# 20_BTB.net
KiCad netlist of a schematic drawn in Altium Designer
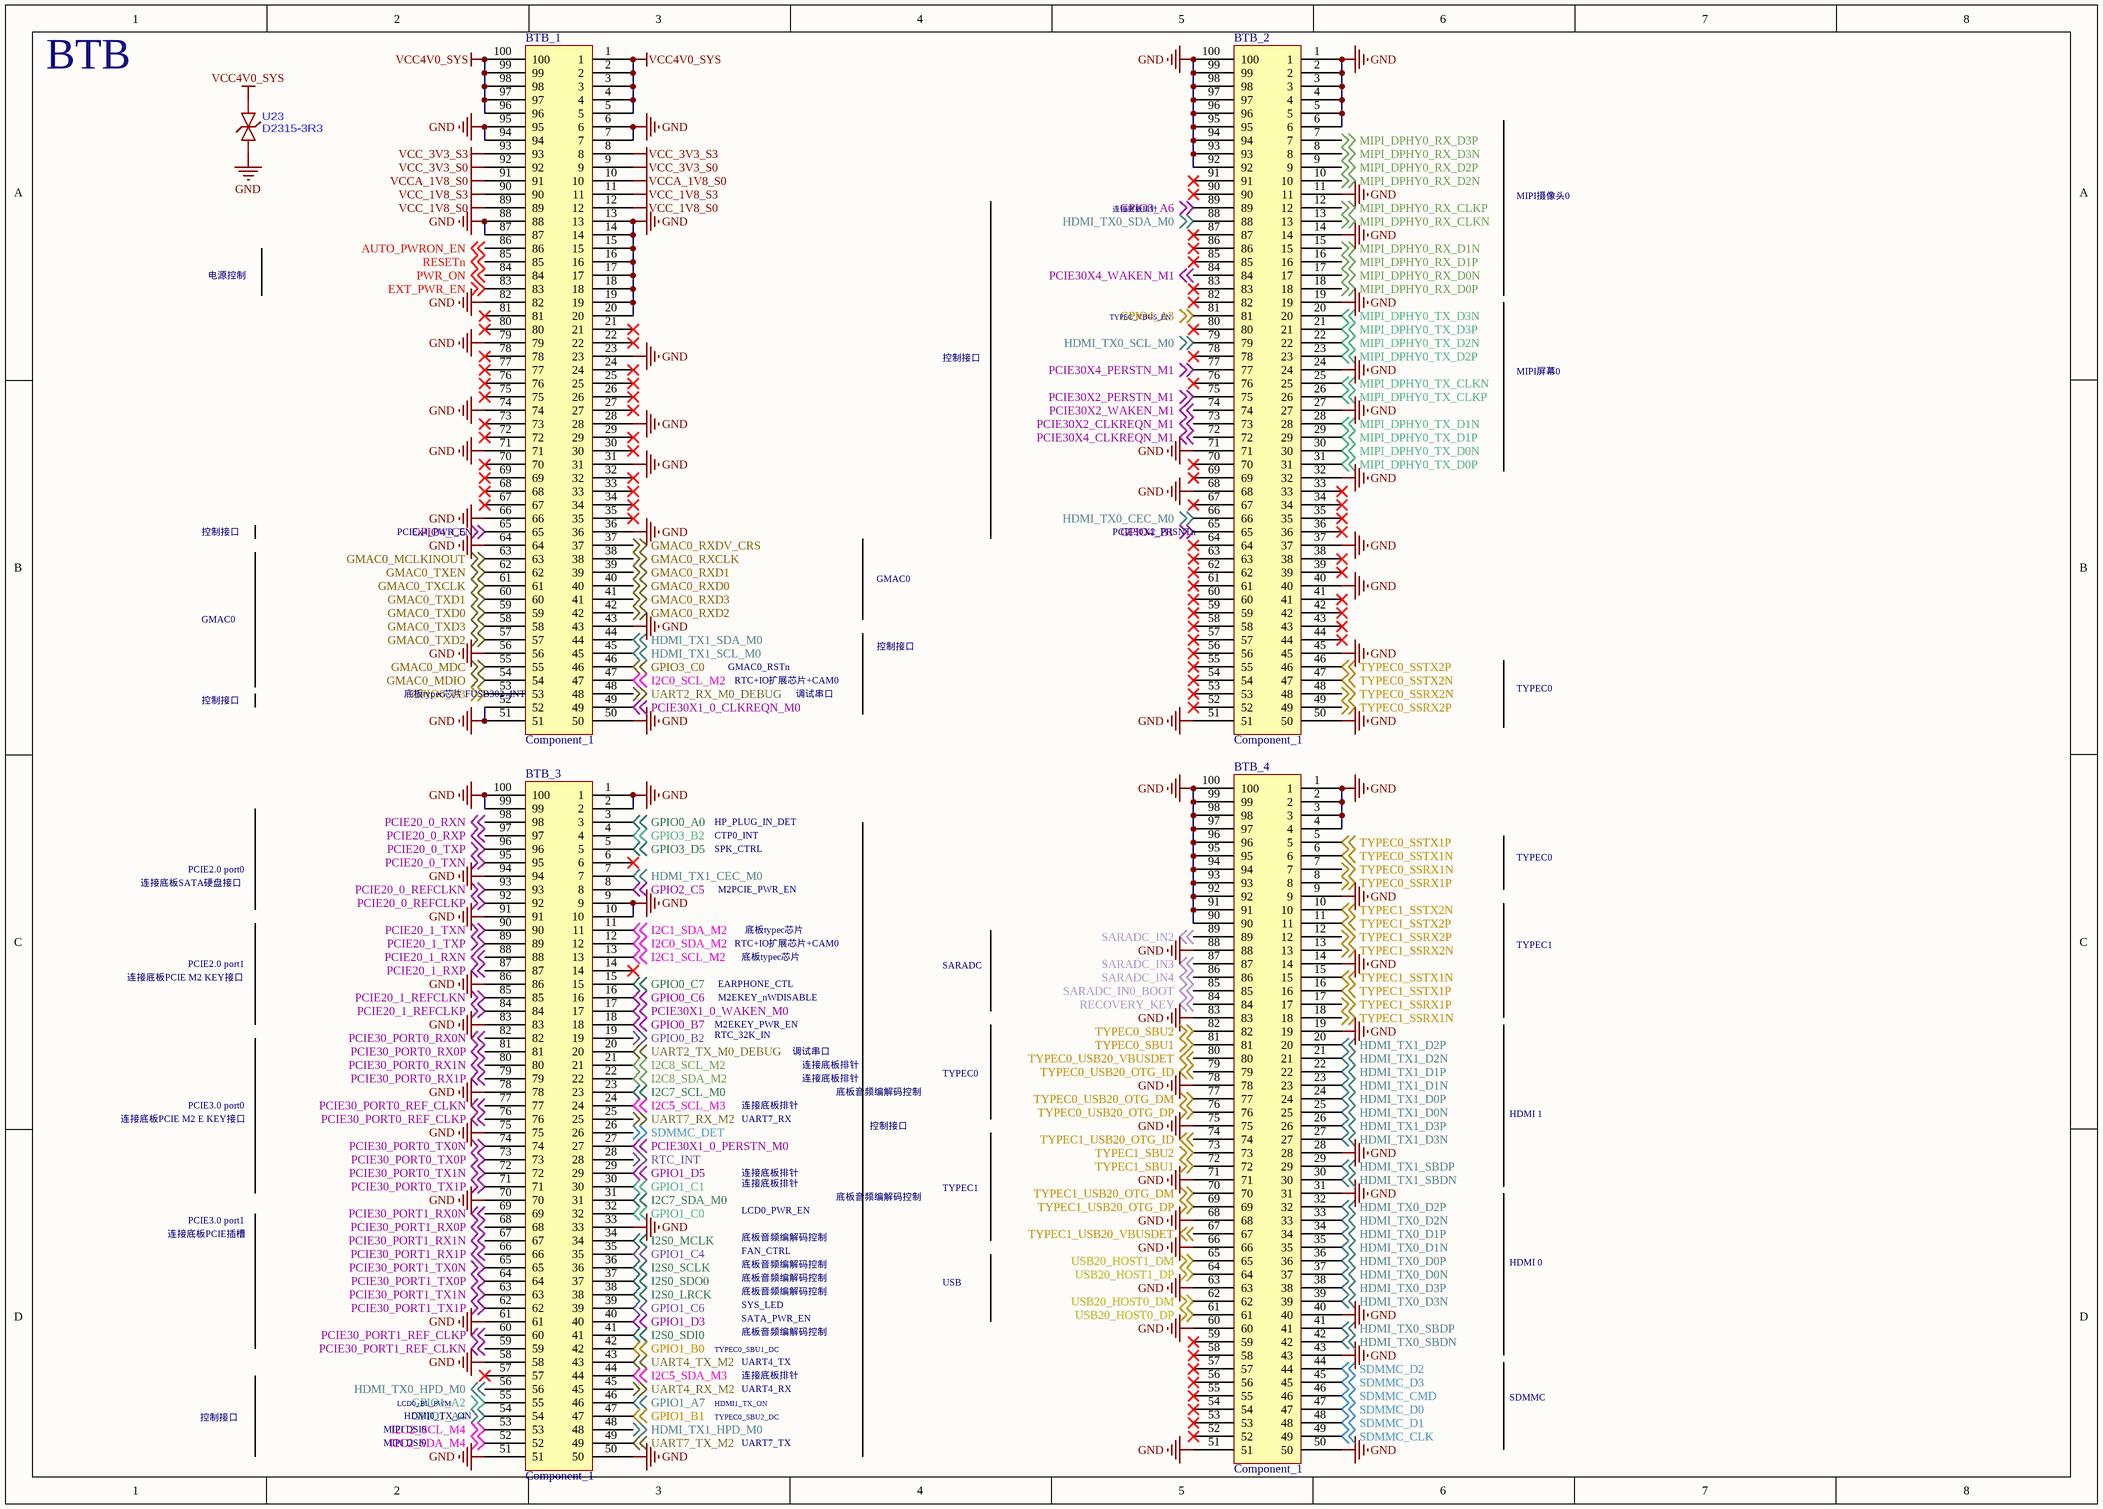
[diagram p0: 20.BTB.SchDoc]

(export (version "E")
  (design (tool "Eeschema 10.0.6"))
  (components
    (comp (ref "BTB_1")
      (value "Component_1")
      (footprint "0.PCB1:F_100PIN")
      (libsource (lib "RK3588") (part "Component_1"))
    )
    (comp (ref "BTB_2")
      (value "Component_1")
      (footprint "0.PCB1:F_100PIN")
      (libsource (lib "RK3588") (part "Component_1"))
    )
    (comp (ref "BTB_3")
      (value "Component_1")
      (footprint "0.PCB1:F_100PIN")
      (libsource (lib "RK3588") (part "Component_1"))
    )
    (comp (ref "BTB_4")
      (value "Component_1")
      (footprint "0.PCB1:F_100PIN")
      (libsource (lib "RK3588") (part "Component_1"))
    )
    (comp (ref "U23")
      (value "D2315-3R3")
      (footprint "0.PCB1:DFN1006-2L-BI")
      (libsource (lib "RK3588") (part "D2315-3R3"))
    )
  )
  (nets
    (net (code "1") (name "AUTO_PWRON_EN") (class "Default")
      (node (ref "BTB_1") (pin "86") (pinfunction "86_86") (pintype "passive"))
    )
    (net (code "2") (name "EXT_PWR_EN") (class "Default")
      (node (ref "BTB_1") (pin "83") (pinfunction "83_83") (pintype "passive"))
    )
    (net (code "3") (name "GMAC0_MCLKINOUT") (class "Default")
      (node (ref "BTB_1") (pin "63") (pinfunction "63_63") (pintype "passive"))
    )
    (net (code "4") (name "GMAC0_MDC") (class "Default")
      (node (ref "BTB_1") (pin "55") (pinfunction "55_55") (pintype "passive"))
    )
    (net (code "5") (name "GMAC0_MDIO") (class "Default")
      (node (ref "BTB_1") (pin "54") (pinfunction "54_54") (pintype "passive"))
    )
    (net (code "6") (name "GMAC0_RXCLK") (class "Default")
      (node (ref "BTB_1") (pin "38") (pinfunction "38_38") (pintype "passive"))
    )
    (net (code "7") (name "GMAC0_RXD0") (class "Default")
      (node (ref "BTB_1") (pin "40") (pinfunction "40_40") (pintype "passive"))
    )
    (net (code "8") (name "GMAC0_RXD1") (class "Default")
      (node (ref "BTB_1") (pin "39") (pinfunction "39_39") (pintype "passive"))
    )
    (net (code "9") (name "GMAC0_RXD2") (class "Default")
      (node (ref "BTB_1") (pin "42") (pinfunction "42_42") (pintype "passive"))
    )
    (net (code "10") (name "GMAC0_RXD3") (class "Default")
      (node (ref "BTB_1") (pin "41") (pinfunction "41_41") (pintype "passive"))
    )
    (net (code "11") (name "GMAC0_RXDV_CRS") (class "Default")
      (node (ref "BTB_1") (pin "37") (pinfunction "37_37") (pintype "passive"))
    )
    (net (code "12") (name "GMAC0_TXCLK") (class "Default")
      (node (ref "BTB_1") (pin "61") (pinfunction "61_61") (pintype "passive"))
    )
    (net (code "13") (name "GMAC0_TXD0") (class "Default")
      (node (ref "BTB_1") (pin "59") (pinfunction "59_59") (pintype "passive"))
    )
    (net (code "14") (name "GMAC0_TXD1") (class "Default")
      (node (ref "BTB_1") (pin "60") (pinfunction "60_60") (pintype "passive"))
    )
    (net (code "15") (name "GMAC0_TXD2") (class "Default")
      (node (ref "BTB_1") (pin "57") (pinfunction "57_57") (pintype "passive"))
    )
    (net (code "16") (name "GMAC0_TXD3") (class "Default")
      (node (ref "BTB_1") (pin "58") (pinfunction "58_58") (pintype "passive"))
    )
    (net (code "17") (name "GMAC0_TXEN") (class "Default")
      (node (ref "BTB_1") (pin "62") (pinfunction "62_62") (pintype "passive"))
    )
    (net (code "18") (name "GND") (class "Default")
      (node (ref "BTB_1") (pin "13") (pinfunction "13_13") (pintype "passive"))
      (node (ref "BTB_1") (pin "14") (pinfunction "14_14") (pintype "passive"))
      (node (ref "BTB_1") (pin "15") (pinfunction "15_15") (pintype "passive"))
      (node (ref "BTB_1") (pin "16") (pinfunction "16_16") (pintype "passive"))
      (node (ref "BTB_1") (pin "17") (pinfunction "17_17") (pintype "passive"))
      (node (ref "BTB_1") (pin "18") (pinfunction "18_18") (pintype "passive"))
      (node (ref "BTB_1") (pin "19") (pinfunction "19_19") (pintype "passive"))
      (node (ref "BTB_1") (pin "20") (pinfunction "20_20") (pintype "passive"))
      (node (ref "BTB_1") (pin "23") (pinfunction "23_23") (pintype "passive"))
      (node (ref "BTB_1") (pin "28") (pinfunction "28_28") (pintype "passive"))
      (node (ref "BTB_1") (pin "31") (pinfunction "31_31") (pintype "passive"))
      (node (ref "BTB_1") (pin "36") (pinfunction "36_36") (pintype "passive"))
      (node (ref "BTB_1") (pin "43") (pinfunction "43_43") (pintype "passive"))
      (node (ref "BTB_1") (pin "50") (pinfunction "50_50") (pintype "passive"))
      (node (ref "BTB_1") (pin "51") (pinfunction "51_51") (pintype "passive"))
      (node (ref "BTB_1") (pin "52") (pinfunction "52_52") (pintype "passive"))
      (node (ref "BTB_1") (pin "56") (pinfunction "56_56") (pintype "passive"))
      (node (ref "BTB_1") (pin "6") (pinfunction "6_6") (pintype "passive"))
      (node (ref "BTB_1") (pin "64") (pinfunction "64_64") (pintype "passive"))
      (node (ref "BTB_1") (pin "66") (pinfunction "66_66") (pintype "passive"))
      (node (ref "BTB_1") (pin "7") (pinfunction "7_7") (pintype "passive"))
      (node (ref "BTB_1") (pin "71") (pinfunction "71_71") (pintype "passive"))
      (node (ref "BTB_1") (pin "74") (pinfunction "74_74") (pintype "passive"))
      (node (ref "BTB_1") (pin "79") (pinfunction "79_79") (pintype "passive"))
      (node (ref "BTB_1") (pin "82") (pinfunction "82_82") (pintype "passive"))
      (node (ref "BTB_1") (pin "87") (pinfunction "87_87") (pintype "passive"))
      (node (ref "BTB_1") (pin "88") (pinfunction "88_88") (pintype "passive"))
      (node (ref "BTB_1") (pin "94") (pinfunction "94_94") (pintype "passive"))
      (node (ref "BTB_1") (pin "95") (pinfunction "95_95") (pintype "passive"))
      (node (ref "BTB_2") (pin "1") (pinfunction "1_1") (pintype "passive"))
      (node (ref "BTB_2") (pin "100") (pinfunction "100_100") (pintype "passive"))
      (node (ref "BTB_2") (pin "11") (pinfunction "11_11") (pintype "passive"))
      (node (ref "BTB_2") (pin "14") (pinfunction "14_14") (pintype "passive"))
      (node (ref "BTB_2") (pin "19") (pinfunction "19_19") (pintype "passive"))
      (node (ref "BTB_2") (pin "2") (pinfunction "2_2") (pintype "passive"))
      (node (ref "BTB_2") (pin "24") (pinfunction "24_24") (pintype "passive"))
      (node (ref "BTB_2") (pin "27") (pinfunction "27_27") (pintype "passive"))
      (node (ref "BTB_2") (pin "3") (pinfunction "3_3") (pintype "passive"))
      (node (ref "BTB_2") (pin "32") (pinfunction "32_32") (pintype "passive"))
      (node (ref "BTB_2") (pin "37") (pinfunction "37_37") (pintype "passive"))
      (node (ref "BTB_2") (pin "4") (pinfunction "4_4") (pintype "passive"))
      (node (ref "BTB_2") (pin "40") (pinfunction "40_40") (pintype "passive"))
      (node (ref "BTB_2") (pin "45") (pinfunction "45_45") (pintype "passive"))
      (node (ref "BTB_2") (pin "5") (pinfunction "5_5") (pintype "passive"))
      (node (ref "BTB_2") (pin "50") (pinfunction "50_50") (pintype "passive"))
      (node (ref "BTB_2") (pin "51") (pinfunction "51_51") (pintype "passive"))
      (node (ref "BTB_2") (pin "6") (pinfunction "6_6") (pintype "passive"))
      (node (ref "BTB_2") (pin "68") (pinfunction "68_68") (pintype "passive"))
      (node (ref "BTB_2") (pin "71") (pinfunction "71_71") (pintype "passive"))
      (node (ref "BTB_2") (pin "92") (pinfunction "92_92") (pintype "passive"))
      (node (ref "BTB_2") (pin "93") (pinfunction "93_93") (pintype "passive"))
      (node (ref "BTB_2") (pin "94") (pinfunction "94_94") (pintype "passive"))
      (node (ref "BTB_2") (pin "95") (pinfunction "95_95") (pintype "passive"))
      (node (ref "BTB_2") (pin "96") (pinfunction "96_96") (pintype "passive"))
      (node (ref "BTB_2") (pin "97") (pinfunction "97_97") (pintype "passive"))
      (node (ref "BTB_2") (pin "98") (pinfunction "98_98") (pintype "passive"))
      (node (ref "BTB_2") (pin "99") (pinfunction "99_99") (pintype "passive"))
      (node (ref "BTB_3") (pin "1") (pinfunction "1_1") (pintype "passive"))
      (node (ref "BTB_3") (pin "10") (pinfunction "10_10") (pintype "passive"))
      (node (ref "BTB_3") (pin "100") (pinfunction "100_100") (pintype "passive"))
      (node (ref "BTB_3") (pin "2") (pinfunction "2_2") (pintype "passive"))
      (node (ref "BTB_3") (pin "33") (pinfunction "33_33") (pintype "passive"))
      (node (ref "BTB_3") (pin "50") (pinfunction "50_50") (pintype "passive"))
      (node (ref "BTB_3") (pin "51") (pinfunction "51_51") (pintype "passive"))
      (node (ref "BTB_3") (pin "58") (pinfunction "58_58") (pintype "passive"))
      (node (ref "BTB_3") (pin "61") (pinfunction "61_61") (pintype "passive"))
      (node (ref "BTB_3") (pin "70") (pinfunction "70_70") (pintype "passive"))
      (node (ref "BTB_3") (pin "75") (pinfunction "75_75") (pintype "passive"))
      (node (ref "BTB_3") (pin "78") (pinfunction "78_78") (pintype "passive"))
      (node (ref "BTB_3") (pin "83") (pinfunction "83_83") (pintype "passive"))
      (node (ref "BTB_3") (pin "86") (pinfunction "86_86") (pintype "passive"))
      (node (ref "BTB_3") (pin "9") (pinfunction "9_9") (pintype "passive"))
      (node (ref "BTB_3") (pin "91") (pinfunction "91_91") (pintype "passive"))
      (node (ref "BTB_3") (pin "94") (pinfunction "94_94") (pintype "passive"))
      (node (ref "BTB_3") (pin "99") (pinfunction "99_99") (pintype "passive"))
      (node (ref "BTB_4") (pin "1") (pinfunction "1_1") (pintype "passive"))
      (node (ref "BTB_4") (pin "100") (pinfunction "100_100") (pintype "passive"))
      (node (ref "BTB_4") (pin "14") (pinfunction "14_14") (pintype "passive"))
      (node (ref "BTB_4") (pin "19") (pinfunction "19_19") (pintype "passive"))
      (node (ref "BTB_4") (pin "2") (pinfunction "2_2") (pintype "passive"))
      (node (ref "BTB_4") (pin "28") (pinfunction "28_28") (pintype "passive"))
      (node (ref "BTB_4") (pin "3") (pinfunction "3_3") (pintype "passive"))
      (node (ref "BTB_4") (pin "31") (pinfunction "31_31") (pintype "passive"))
      (node (ref "BTB_4") (pin "4") (pinfunction "4_4") (pintype "passive"))
      (node (ref "BTB_4") (pin "40") (pinfunction "40_40") (pintype "passive"))
      (node (ref "BTB_4") (pin "43") (pinfunction "43_43") (pintype "passive"))
      (node (ref "BTB_4") (pin "50") (pinfunction "50_50") (pintype "passive"))
      (node (ref "BTB_4") (pin "51") (pinfunction "51_51") (pintype "passive"))
      (node (ref "BTB_4") (pin "60") (pinfunction "60_60") (pintype "passive"))
      (node (ref "BTB_4") (pin "63") (pinfunction "63_63") (pintype "passive"))
      (node (ref "BTB_4") (pin "66") (pinfunction "66_66") (pintype "passive"))
      (node (ref "BTB_4") (pin "68") (pinfunction "68_68") (pintype "passive"))
      (node (ref "BTB_4") (pin "71") (pinfunction "71_71") (pintype "passive"))
      (node (ref "BTB_4") (pin "75") (pinfunction "75_75") (pintype "passive"))
      (node (ref "BTB_4") (pin "78") (pinfunction "78_78") (pintype "passive"))
      (node (ref "BTB_4") (pin "83") (pinfunction "83_83") (pintype "passive"))
      (node (ref "BTB_4") (pin "88") (pinfunction "88_88") (pintype "passive"))
      (node (ref "BTB_4") (pin "9") (pinfunction "9_9") (pintype "passive"))
      (node (ref "BTB_4") (pin "90") (pinfunction "90_90") (pintype "passive"))
      (node (ref "BTB_4") (pin "91") (pinfunction "91_91") (pintype "passive"))
      (node (ref "BTB_4") (pin "92") (pinfunction "92_92") (pintype "passive"))
      (node (ref "BTB_4") (pin "93") (pinfunction "93_93") (pintype "passive"))
      (node (ref "BTB_4") (pin "94") (pinfunction "94_94") (pintype "passive"))
      (node (ref "BTB_4") (pin "95") (pinfunction "95_95") (pintype "passive"))
      (node (ref "BTB_4") (pin "96") (pinfunction "96_96") (pintype "passive"))
      (node (ref "BTB_4") (pin "97") (pinfunction "97_97") (pintype "passive"))
      (node (ref "BTB_4") (pin "98") (pinfunction "98_98") (pintype "passive"))
      (node (ref "BTB_4") (pin "99") (pinfunction "99_99") (pintype "passive"))
      (node (ref "U23") (pin "1") (pinfunction "1_1") (pintype "passive"))
    )
    (net (code "19") (name "GPIO0_A0") (class "Default")
      (node (ref "BTB_3") (pin "3") (pinfunction "3_3") (pintype "passive"))
    )
    (net (code "20") (name "GPIO0_B2") (class "Default")
      (node (ref "BTB_3") (pin "19") (pinfunction "19_19") (pintype "passive"))
    )
    (net (code "21") (name "GPIO0_B7") (class "Default")
      (node (ref "BTB_3") (pin "18") (pinfunction "18_18") (pintype "passive"))
    )
    (net (code "22") (name "GPIO0_C6") (class "Default")
      (node (ref "BTB_3") (pin "16") (pinfunction "16_16") (pintype "passive"))
    )
    (net (code "23") (name "GPIO0_C7") (class "Default")
      (node (ref "BTB_3") (pin "15") (pinfunction "15_15") (pintype "passive"))
    )
    (net (code "24") (name "GPIO0_D3") (class "Default")
      (node (ref "BTB_1") (pin "53") (pinfunction "53_53") (pintype "passive"))
    )
    (net (code "25") (name "GPIO1_A2") (class "Default")
      (node (ref "BTB_3") (pin "55") (pinfunction "55_55") (pintype "passive"))
    )
    (net (code "26") (name "GPIO1_A4") (class "Default")
      (node (ref "BTB_3") (pin "54") (pinfunction "54_54") (pintype "passive"))
    )
    (net (code "27") (name "GPIO1_A7") (class "Default")
      (node (ref "BTB_3") (pin "46") (pinfunction "46_46") (pintype "passive"))
    )
    (net (code "28") (name "GPIO1_B0") (class "Default")
      (node (ref "BTB_3") (pin "42") (pinfunction "42_42") (pintype "passive"))
    )
    (net (code "29") (name "GPIO1_B1") (class "Default")
      (node (ref "BTB_3") (pin "47") (pinfunction "47_47") (pintype "passive"))
    )
    (net (code "30") (name "GPIO1_C0") (class "Default")
      (node (ref "BTB_3") (pin "32") (pinfunction "32_32") (pintype "passive"))
    )
    (net (code "31") (name "GPIO1_C1") (class "Default")
      (node (ref "BTB_3") (pin "30") (pinfunction "30_30") (pintype "passive"))
    )
    (net (code "32") (name "GPIO1_C4") (class "Default")
      (node (ref "BTB_3") (pin "35") (pinfunction "35_35") (pintype "passive"))
    )
    (net (code "33") (name "GPIO1_C6") (class "Default")
      (node (ref "BTB_3") (pin "39") (pinfunction "39_39") (pintype "passive"))
    )
    (net (code "34") (name "GPIO1_D3") (class "Default")
      (node (ref "BTB_3") (pin "40") (pinfunction "40_40") (pintype "passive"))
    )
    (net (code "35") (name "GPIO1_D5") (class "Default")
      (node (ref "BTB_3") (pin "29") (pinfunction "29_29") (pintype "passive"))
    )
    (net (code "36") (name "GPIO2_C5") (class "Default")
      (node (ref "BTB_3") (pin "8") (pinfunction "8_8") (pintype "passive"))
    )
    (net (code "37") (name "GPIO3_A6") (class "Default")
      (node (ref "BTB_2") (pin "89") (pinfunction "89_89") (pintype "passive"))
    )
    (net (code "38") (name "GPIO3_B2") (class "Default")
      (node (ref "BTB_3") (pin "4") (pinfunction "4_4") (pintype "passive"))
    )
    (net (code "39") (name "GPIO3_C0") (class "Default")
      (node (ref "BTB_1") (pin "46") (pinfunction "46_46") (pintype "passive"))
    )
    (net (code "40") (name "GPIO3_D5") (class "Default")
      (node (ref "BTB_3") (pin "5") (pinfunction "5_5") (pintype "passive"))
    )
    (net (code "41") (name "GPIO4_A3") (class "Default")
      (node (ref "BTB_2") (pin "81") (pinfunction "81_81") (pintype "passive"))
    )
    (net (code "42") (name "GPIO4_B1") (class "Default")
      (node (ref "BTB_2") (pin "65") (pinfunction "65_65") (pintype "passive"))
    )
    (net (code "43") (name "GPIO4_C6") (class "Default")
      (node (ref "BTB_1") (pin "65") (pinfunction "65_65") (pintype "passive"))
    )
    (net (code "44") (name "HDMI_TX0_CEC_M0") (class "Default")
      (node (ref "BTB_2") (pin "66") (pinfunction "66_66") (pintype "passive"))
    )
    (net (code "45") (name "HDMI_TX0_D0N") (class "Default")
      (node (ref "BTB_4") (pin "37") (pinfunction "37_37") (pintype "passive"))
    )
    (net (code "46") (name "HDMI_TX0_D0P") (class "Default")
      (node (ref "BTB_4") (pin "36") (pinfunction "36_36") (pintype "passive"))
    )
    (net (code "47") (name "HDMI_TX0_D1N") (class "Default")
      (node (ref "BTB_4") (pin "35") (pinfunction "35_35") (pintype "passive"))
    )
    (net (code "48") (name "HDMI_TX0_D1P") (class "Default")
      (node (ref "BTB_4") (pin "34") (pinfunction "34_34") (pintype "passive"))
    )
    (net (code "49") (name "HDMI_TX0_D2N") (class "Default")
      (node (ref "BTB_4") (pin "33") (pinfunction "33_33") (pintype "passive"))
    )
    (net (code "50") (name "HDMI_TX0_D2P") (class "Default")
      (node (ref "BTB_4") (pin "32") (pinfunction "32_32") (pintype "passive"))
    )
    (net (code "51") (name "HDMI_TX0_D3N") (class "Default")
      (node (ref "BTB_4") (pin "39") (pinfunction "39_39") (pintype "passive"))
    )
    (net (code "52") (name "HDMI_TX0_D3P") (class "Default")
      (node (ref "BTB_4") (pin "38") (pinfunction "38_38") (pintype "passive"))
    )
    (net (code "53") (name "HDMI_TX0_HPD_M0") (class "Default")
      (node (ref "BTB_3") (pin "56") (pinfunction "56_56") (pintype "passive"))
    )
    (net (code "54") (name "HDMI_TX0_SBDN") (class "Default")
      (node (ref "BTB_4") (pin "42") (pinfunction "42_42") (pintype "passive"))
    )
    (net (code "55") (name "HDMI_TX0_SBDP") (class "Default")
      (node (ref "BTB_4") (pin "41") (pinfunction "41_41") (pintype "passive"))
    )
    (net (code "56") (name "HDMI_TX0_SCL_M0") (class "Default")
      (node (ref "BTB_2") (pin "79") (pinfunction "79_79") (pintype "passive"))
    )
    (net (code "57") (name "HDMI_TX0_SDA_M0") (class "Default")
      (node (ref "BTB_2") (pin "88") (pinfunction "88_88") (pintype "passive"))
    )
    (net (code "58") (name "HDMI_TX1_CEC_M0") (class "Default")
      (node (ref "BTB_3") (pin "7") (pinfunction "7_7") (pintype "passive"))
    )
    (net (code "59") (name "HDMI_TX1_D0N") (class "Default")
      (node (ref "BTB_4") (pin "25") (pinfunction "25_25") (pintype "passive"))
    )
    (net (code "60") (name "HDMI_TX1_D0P") (class "Default")
      (node (ref "BTB_4") (pin "24") (pinfunction "24_24") (pintype "passive"))
    )
    (net (code "61") (name "HDMI_TX1_D1N") (class "Default")
      (node (ref "BTB_4") (pin "23") (pinfunction "23_23") (pintype "passive"))
    )
    (net (code "62") (name "HDMI_TX1_D1P") (class "Default")
      (node (ref "BTB_4") (pin "22") (pinfunction "22_22") (pintype "passive"))
    )
    (net (code "63") (name "HDMI_TX1_D2N") (class "Default")
      (node (ref "BTB_4") (pin "21") (pinfunction "21_21") (pintype "passive"))
    )
    (net (code "64") (name "HDMI_TX1_D2P") (class "Default")
      (node (ref "BTB_4") (pin "20") (pinfunction "20_20") (pintype "passive"))
    )
    (net (code "65") (name "HDMI_TX1_D3N") (class "Default")
      (node (ref "BTB_4") (pin "27") (pinfunction "27_27") (pintype "passive"))
    )
    (net (code "66") (name "HDMI_TX1_D3P") (class "Default")
      (node (ref "BTB_4") (pin "26") (pinfunction "26_26") (pintype "passive"))
    )
    (net (code "67") (name "HDMI_TX1_HPD_M0") (class "Default")
      (node (ref "BTB_3") (pin "48") (pinfunction "48_48") (pintype "passive"))
    )
    (net (code "68") (name "HDMI_TX1_SBDN") (class "Default")
      (node (ref "BTB_4") (pin "30") (pinfunction "30_30") (pintype "passive"))
    )
    (net (code "69") (name "HDMI_TX1_SBDP") (class "Default")
      (node (ref "BTB_4") (pin "29") (pinfunction "29_29") (pintype "passive"))
    )
    (net (code "70") (name "HDMI_TX1_SCL_M0") (class "Default")
      (node (ref "BTB_1") (pin "45") (pinfunction "45_45") (pintype "passive"))
    )
    (net (code "71") (name "HDMI_TX1_SDA_M0") (class "Default")
      (node (ref "BTB_1") (pin "44") (pinfunction "44_44") (pintype "passive"))
    )
    (net (code "72") (name "I2C0_SCL_M2") (class "Default")
      (node (ref "BTB_1") (pin "47") (pinfunction "47_47") (pintype "passive"))
    )
    (net (code "73") (name "I2C0_SDA_M2") (class "Default")
      (node (ref "BTB_3") (pin "12") (pinfunction "12_12") (pintype "passive"))
    )
    (net (code "74") (name "I2C1_SCL_M2") (class "Default")
      (node (ref "BTB_3") (pin "13") (pinfunction "13_13") (pintype "passive"))
    )
    (net (code "75") (name "I2C1_SDA_M2") (class "Default")
      (node (ref "BTB_3") (pin "11") (pinfunction "11_11") (pintype "passive"))
    )
    (net (code "76") (name "I2C2_SCL_M4") (class "Default")
      (node (ref "BTB_3") (pin "53") (pinfunction "53_53") (pintype "passive"))
    )
    (net (code "77") (name "I2C2_SDA_M4") (class "Default")
      (node (ref "BTB_3") (pin "52") (pinfunction "52_52") (pintype "passive"))
    )
    (net (code "78") (name "I2C5_SCL_M3") (class "Default")
      (node (ref "BTB_3") (pin "24") (pinfunction "24_24") (pintype "passive"))
    )
    (net (code "79") (name "I2C5_SDA_M3") (class "Default")
      (node (ref "BTB_3") (pin "44") (pinfunction "44_44") (pintype "passive"))
    )
    (net (code "80") (name "I2C7_SCL_M0") (class "Default")
      (node (ref "BTB_3") (pin "23") (pinfunction "23_23") (pintype "passive"))
    )
    (net (code "81") (name "I2C7_SDA_M0") (class "Default")
      (node (ref "BTB_3") (pin "31") (pinfunction "31_31") (pintype "passive"))
    )
    (net (code "82") (name "I2C8_SCL_M2") (class "Default")
      (node (ref "BTB_3") (pin "21") (pinfunction "21_21") (pintype "passive"))
    )
    (net (code "83") (name "I2C8_SDA_M2") (class "Default")
      (node (ref "BTB_3") (pin "22") (pinfunction "22_22") (pintype "passive"))
    )
    (net (code "84") (name "I2S0_LRCK") (class "Default")
      (node (ref "BTB_3") (pin "38") (pinfunction "38_38") (pintype "passive"))
    )
    (net (code "85") (name "I2S0_MCLK") (class "Default")
      (node (ref "BTB_3") (pin "34") (pinfunction "34_34") (pintype "passive"))
    )
    (net (code "86") (name "I2S0_SCLK") (class "Default")
      (node (ref "BTB_3") (pin "36") (pinfunction "36_36") (pintype "passive"))
    )
    (net (code "87") (name "I2S0_SDI0") (class "Default")
      (node (ref "BTB_3") (pin "41") (pinfunction "41_41") (pintype "passive"))
    )
    (net (code "88") (name "I2S0_SDO0") (class "Default")
      (node (ref "BTB_3") (pin "37") (pinfunction "37_37") (pintype "passive"))
    )
    (net (code "89") (name "MIPI_DPHY0_RX_CLKN") (class "Default")
      (node (ref "BTB_2") (pin "13") (pinfunction "13_13") (pintype "passive"))
    )
    (net (code "90") (name "MIPI_DPHY0_RX_CLKP") (class "Default")
      (node (ref "BTB_2") (pin "12") (pinfunction "12_12") (pintype "passive"))
    )
    (net (code "91") (name "MIPI_DPHY0_RX_D0N") (class "Default")
      (node (ref "BTB_2") (pin "17") (pinfunction "17_17") (pintype "passive"))
    )
    (net (code "92") (name "MIPI_DPHY0_RX_D0P") (class "Default")
      (node (ref "BTB_2") (pin "18") (pinfunction "18_18") (pintype "passive"))
    )
    (net (code "93") (name "MIPI_DPHY0_RX_D1N") (class "Default")
      (node (ref "BTB_2") (pin "15") (pinfunction "15_15") (pintype "passive"))
    )
    (net (code "94") (name "MIPI_DPHY0_RX_D1P") (class "Default")
      (node (ref "BTB_2") (pin "16") (pinfunction "16_16") (pintype "passive"))
    )
    (net (code "95") (name "MIPI_DPHY0_RX_D2N") (class "Default")
      (node (ref "BTB_2") (pin "10") (pinfunction "10_10") (pintype "passive"))
    )
    (net (code "96") (name "MIPI_DPHY0_RX_D2P") (class "Default")
      (node (ref "BTB_2") (pin "9") (pinfunction "9_9") (pintype "passive"))
    )
    (net (code "97") (name "MIPI_DPHY0_RX_D3N") (class "Default")
      (node (ref "BTB_2") (pin "8") (pinfunction "8_8") (pintype "passive"))
    )
    (net (code "98") (name "MIPI_DPHY0_RX_D3P") (class "Default")
      (node (ref "BTB_2") (pin "7") (pinfunction "7_7") (pintype "passive"))
    )
    (net (code "99") (name "MIPI_DPHY0_TX_CLKN") (class "Default")
      (node (ref "BTB_2") (pin "25") (pinfunction "25_25") (pintype "passive"))
    )
    (net (code "100") (name "MIPI_DPHY0_TX_CLKP") (class "Default")
      (node (ref "BTB_2") (pin "26") (pinfunction "26_26") (pintype "passive"))
    )
    (net (code "101") (name "MIPI_DPHY0_TX_D0N") (class "Default")
      (node (ref "BTB_2") (pin "30") (pinfunction "30_30") (pintype "passive"))
    )
    (net (code "102") (name "MIPI_DPHY0_TX_D0P") (class "Default")
      (node (ref "BTB_2") (pin "31") (pinfunction "31_31") (pintype "passive"))
    )
    (net (code "103") (name "MIPI_DPHY0_TX_D1N") (class "Default")
      (node (ref "BTB_2") (pin "28") (pinfunction "28_28") (pintype "passive"))
    )
    (net (code "104") (name "MIPI_DPHY0_TX_D1P") (class "Default")
      (node (ref "BTB_2") (pin "29") (pinfunction "29_29") (pintype "passive"))
    )
    (net (code "105") (name "MIPI_DPHY0_TX_D2N") (class "Default")
      (node (ref "BTB_2") (pin "22") (pinfunction "22_22") (pintype "passive"))
    )
    (net (code "106") (name "MIPI_DPHY0_TX_D2P") (class "Default")
      (node (ref "BTB_2") (pin "23") (pinfunction "23_23") (pintype "passive"))
    )
    (net (code "107") (name "MIPI_DPHY0_TX_D3N") (class "Default")
      (node (ref "BTB_2") (pin "20") (pinfunction "20_20") (pintype "passive"))
    )
    (net (code "108") (name "MIPI_DPHY0_TX_D3P") (class "Default")
      (node (ref "BTB_2") (pin "21") (pinfunction "21_21") (pintype "passive"))
    )
    (net (code "109") (name "PCIE20_0_REFCLKN") (class "Default")
      (node (ref "BTB_3") (pin "93") (pinfunction "93_93") (pintype "passive"))
    )
    (net (code "110") (name "PCIE20_0_REFCLKP") (class "Default")
      (node (ref "BTB_3") (pin "92") (pinfunction "92_92") (pintype "passive"))
    )
    (net (code "111") (name "PCIE20_0_RXN") (class "Default")
      (node (ref "BTB_3") (pin "98") (pinfunction "98_98") (pintype "passive"))
    )
    (net (code "112") (name "PCIE20_0_RXP") (class "Default")
      (node (ref "BTB_3") (pin "97") (pinfunction "97_97") (pintype "passive"))
    )
    (net (code "113") (name "PCIE20_0_TXN") (class "Default")
      (node (ref "BTB_3") (pin "95") (pinfunction "95_95") (pintype "passive"))
    )
    (net (code "114") (name "PCIE20_0_TXP") (class "Default")
      (node (ref "BTB_3") (pin "96") (pinfunction "96_96") (pintype "passive"))
    )
    (net (code "115") (name "PCIE20_1_REFCLKN") (class "Default")
      (node (ref "BTB_3") (pin "85") (pinfunction "85_85") (pintype "passive"))
    )
    (net (code "116") (name "PCIE20_1_REFCLKP") (class "Default")
      (node (ref "BTB_3") (pin "84") (pinfunction "84_84") (pintype "passive"))
    )
    (net (code "117") (name "PCIE20_1_RXN") (class "Default")
      (node (ref "BTB_3") (pin "88") (pinfunction "88_88") (pintype "passive"))
    )
    (net (code "118") (name "PCIE20_1_RXP") (class "Default")
      (node (ref "BTB_3") (pin "87") (pinfunction "87_87") (pintype "passive"))
    )
    (net (code "119") (name "PCIE20_1_TXN") (class "Default")
      (node (ref "BTB_3") (pin "90") (pinfunction "90_90") (pintype "passive"))
    )
    (net (code "120") (name "PCIE20_1_TXP") (class "Default")
      (node (ref "BTB_3") (pin "89") (pinfunction "89_89") (pintype "passive"))
    )
    (net (code "121") (name "PCIE30X1_0_CLKREQN_M0") (class "Default")
      (node (ref "BTB_1") (pin "49") (pinfunction "49_49") (pintype "passive"))
    )
    (net (code "122") (name "PCIE30X1_0_PERSTN_M0") (class "Default")
      (node (ref "BTB_3") (pin "27") (pinfunction "27_27") (pintype "passive"))
    )
    (net (code "123") (name "PCIE30X1_0_WAKEN_M0") (class "Default")
      (node (ref "BTB_3") (pin "17") (pinfunction "17_17") (pintype "passive"))
    )
    (net (code "124") (name "PCIE30X2_CLKREQN_M1") (class "Default")
      (node (ref "BTB_2") (pin "73") (pinfunction "73_73") (pintype "passive"))
    )
    (net (code "125") (name "PCIE30X2_PERSTN_M1") (class "Default")
      (node (ref "BTB_2") (pin "75") (pinfunction "75_75") (pintype "passive"))
    )
    (net (code "126") (name "PCIE30X2_WAKEN_M1") (class "Default")
      (node (ref "BTB_2") (pin "74") (pinfunction "74_74") (pintype "passive"))
    )
    (net (code "127") (name "PCIE30X4_CLKREQN_M1") (class "Default")
      (node (ref "BTB_2") (pin "72") (pinfunction "72_72") (pintype "passive"))
    )
    (net (code "128") (name "PCIE30X4_PERSTN_M1") (class "Default")
      (node (ref "BTB_2") (pin "77") (pinfunction "77_77") (pintype "passive"))
    )
    (net (code "129") (name "PCIE30X4_WAKEN_M1") (class "Default")
      (node (ref "BTB_2") (pin "84") (pinfunction "84_84") (pintype "passive"))
    )
    (net (code "130") (name "PCIE30_PORT0_REF_CLKN") (class "Default")
      (node (ref "BTB_3") (pin "77") (pinfunction "77_77") (pintype "passive"))
    )
    (net (code "131") (name "PCIE30_PORT0_REF_CLKP") (class "Default")
      (node (ref "BTB_3") (pin "76") (pinfunction "76_76") (pintype "passive"))
    )
    (net (code "132") (name "PCIE30_PORT0_RX0N") (class "Default")
      (node (ref "BTB_3") (pin "82") (pinfunction "82_82") (pintype "passive"))
    )
    (net (code "133") (name "PCIE30_PORT0_RX0P") (class "Default")
      (node (ref "BTB_3") (pin "81") (pinfunction "81_81") (pintype "passive"))
    )
    (net (code "134") (name "PCIE30_PORT0_RX1N") (class "Default")
      (node (ref "BTB_3") (pin "80") (pinfunction "80_80") (pintype "passive"))
    )
    (net (code "135") (name "PCIE30_PORT0_RX1P") (class "Default")
      (node (ref "BTB_3") (pin "79") (pinfunction "79_79") (pintype "passive"))
    )
    (net (code "136") (name "PCIE30_PORT0_TX0N") (class "Default")
      (node (ref "BTB_3") (pin "74") (pinfunction "74_74") (pintype "passive"))
    )
    (net (code "137") (name "PCIE30_PORT0_TX0P") (class "Default")
      (node (ref "BTB_3") (pin "73") (pinfunction "73_73") (pintype "passive"))
    )
    (net (code "138") (name "PCIE30_PORT0_TX1N") (class "Default")
      (node (ref "BTB_3") (pin "72") (pinfunction "72_72") (pintype "passive"))
    )
    (net (code "139") (name "PCIE30_PORT0_TX1P") (class "Default")
      (node (ref "BTB_3") (pin "71") (pinfunction "71_71") (pintype "passive"))
    )
    (net (code "140") (name "PCIE30_PORT1_REF_CLKN") (class "Default")
      (node (ref "BTB_3") (pin "59") (pinfunction "59_59") (pintype "passive"))
    )
    (net (code "141") (name "PCIE30_PORT1_REF_CLKP") (class "Default")
      (node (ref "BTB_3") (pin "60") (pinfunction "60_60") (pintype "passive"))
    )
    (net (code "142") (name "PCIE30_PORT1_RX0N") (class "Default")
      (node (ref "BTB_3") (pin "69") (pinfunction "69_69") (pintype "passive"))
    )
    (net (code "143") (name "PCIE30_PORT1_RX0P") (class "Default")
      (node (ref "BTB_3") (pin "68") (pinfunction "68_68") (pintype "passive"))
    )
    (net (code "144") (name "PCIE30_PORT1_RX1N") (class "Default")
      (node (ref "BTB_3") (pin "67") (pinfunction "67_67") (pintype "passive"))
    )
    (net (code "145") (name "PCIE30_PORT1_RX1P") (class "Default")
      (node (ref "BTB_3") (pin "66") (pinfunction "66_66") (pintype "passive"))
    )
    (net (code "146") (name "PCIE30_PORT1_TX0N") (class "Default")
      (node (ref "BTB_3") (pin "65") (pinfunction "65_65") (pintype "passive"))
    )
    (net (code "147") (name "PCIE30_PORT1_TX0P") (class "Default")
      (node (ref "BTB_3") (pin "64") (pinfunction "64_64") (pintype "passive"))
    )
    (net (code "148") (name "PCIE30_PORT1_TX1N") (class "Default")
      (node (ref "BTB_3") (pin "63") (pinfunction "63_63") (pintype "passive"))
    )
    (net (code "149") (name "PCIE30_PORT1_TX1P") (class "Default")
      (node (ref "BTB_3") (pin "62") (pinfunction "62_62") (pintype "passive"))
    )
    (net (code "150") (name "PWR_ON") (class "Default")
      (node (ref "BTB_1") (pin "84") (pinfunction "84_84") (pintype "passive"))
    )
    (net (code "151") (name "RECOVERY_KEY") (class "Default")
      (node (ref "BTB_4") (pin "84") (pinfunction "84_84") (pintype "passive"))
    )
    (net (code "152") (name "RESETn") (class "Default")
      (node (ref "BTB_1") (pin "85") (pinfunction "85_85") (pintype "passive"))
    )
    (net (code "153") (name "RTC_INT") (class "Default")
      (node (ref "BTB_3") (pin "28") (pinfunction "28_28") (pintype "passive"))
    )
    (net (code "154") (name "SARADC_IN0_BOOT") (class "Default")
      (node (ref "BTB_4") (pin "85") (pinfunction "85_85") (pintype "passive"))
    )
    (net (code "155") (name "SARADC_IN2") (class "Default")
      (node (ref "BTB_4") (pin "89") (pinfunction "89_89") (pintype "passive"))
    )
    (net (code "156") (name "SARADC_IN3") (class "Default")
      (node (ref "BTB_4") (pin "87") (pinfunction "87_87") (pintype "passive"))
    )
    (net (code "157") (name "SARADC_IN4") (class "Default")
      (node (ref "BTB_4") (pin "86") (pinfunction "86_86") (pintype "passive"))
    )
    (net (code "158") (name "SDMMC_CLK") (class "Default")
      (node (ref "BTB_4") (pin "49") (pinfunction "49_49") (pintype "passive"))
    )
    (net (code "159") (name "SDMMC_CMD") (class "Default")
      (node (ref "BTB_4") (pin "46") (pinfunction "46_46") (pintype "passive"))
    )
    (net (code "160") (name "SDMMC_D0") (class "Default")
      (node (ref "BTB_4") (pin "47") (pinfunction "47_47") (pintype "passive"))
    )
    (net (code "161") (name "SDMMC_D1") (class "Default")
      (node (ref "BTB_4") (pin "48") (pinfunction "48_48") (pintype "passive"))
    )
    (net (code "162") (name "SDMMC_D2") (class "Default")
      (node (ref "BTB_4") (pin "44") (pinfunction "44_44") (pintype "passive"))
    )
    (net (code "163") (name "SDMMC_D3") (class "Default")
      (node (ref "BTB_4") (pin "45") (pinfunction "45_45") (pintype "passive"))
    )
    (net (code "164") (name "SDMMC_DET") (class "Default")
      (node (ref "BTB_3") (pin "26") (pinfunction "26_26") (pintype "passive"))
    )
    (net (code "165") (name "TYPEC0_SBU1") (class "Default")
      (node (ref "BTB_4") (pin "81") (pinfunction "81_81") (pintype "passive"))
    )
    (net (code "166") (name "TYPEC0_SBU2") (class "Default")
      (node (ref "BTB_4") (pin "82") (pinfunction "82_82") (pintype "passive"))
    )
    (net (code "167") (name "TYPEC0_SSRX1N") (class "Default")
      (node (ref "BTB_4") (pin "7") (pinfunction "7_7") (pintype "passive"))
    )
    (net (code "168") (name "TYPEC0_SSRX1P") (class "Default")
      (node (ref "BTB_4") (pin "8") (pinfunction "8_8") (pintype "passive"))
    )
    (net (code "169") (name "TYPEC0_SSRX2N") (class "Default")
      (node (ref "BTB_2") (pin "48") (pinfunction "48_48") (pintype "passive"))
    )
    (net (code "170") (name "TYPEC0_SSRX2P") (class "Default")
      (node (ref "BTB_2") (pin "49") (pinfunction "49_49") (pintype "passive"))
    )
    (net (code "171") (name "TYPEC0_SSTX1N") (class "Default")
      (node (ref "BTB_4") (pin "6") (pinfunction "6_6") (pintype "passive"))
    )
    (net (code "172") (name "TYPEC0_SSTX1P") (class "Default")
      (node (ref "BTB_4") (pin "5") (pinfunction "5_5") (pintype "passive"))
    )
    (net (code "173") (name "TYPEC0_SSTX2N") (class "Default")
      (node (ref "BTB_2") (pin "47") (pinfunction "47_47") (pintype "passive"))
    )
    (net (code "174") (name "TYPEC0_SSTX2P") (class "Default")
      (node (ref "BTB_2") (pin "46") (pinfunction "46_46") (pintype "passive"))
    )
    (net (code "175") (name "TYPEC0_USB20_OTG_DM") (class "Default")
      (node (ref "BTB_4") (pin "77") (pinfunction "77_77") (pintype "passive"))
    )
    (net (code "176") (name "TYPEC0_USB20_OTG_DP") (class "Default")
      (node (ref "BTB_4") (pin "76") (pinfunction "76_76") (pintype "passive"))
    )
    (net (code "177") (name "TYPEC0_USB20_OTG_ID") (class "Default")
      (node (ref "BTB_4") (pin "79") (pinfunction "79_79") (pintype "passive"))
    )
    (net (code "178") (name "TYPEC0_USB20_VBUSDET") (class "Default")
      (node (ref "BTB_4") (pin "80") (pinfunction "80_80") (pintype "passive"))
    )
    (net (code "179") (name "TYPEC1_SBU1") (class "Default")
      (node (ref "BTB_4") (pin "72") (pinfunction "72_72") (pintype "passive"))
    )
    (net (code "180") (name "TYPEC1_SBU2") (class "Default")
      (node (ref "BTB_4") (pin "73") (pinfunction "73_73") (pintype "passive"))
    )
    (net (code "181") (name "TYPEC1_SSRX1N") (class "Default")
      (node (ref "BTB_4") (pin "18") (pinfunction "18_18") (pintype "passive"))
    )
    (net (code "182") (name "TYPEC1_SSRX1P") (class "Default")
      (node (ref "BTB_4") (pin "17") (pinfunction "17_17") (pintype "passive"))
    )
    (net (code "183") (name "TYPEC1_SSRX2N") (class "Default")
      (node (ref "BTB_4") (pin "13") (pinfunction "13_13") (pintype "passive"))
    )
    (net (code "184") (name "TYPEC1_SSRX2P") (class "Default")
      (node (ref "BTB_4") (pin "12") (pinfunction "12_12") (pintype "passive"))
    )
    (net (code "185") (name "TYPEC1_SSTX1N") (class "Default")
      (node (ref "BTB_4") (pin "15") (pinfunction "15_15") (pintype "passive"))
    )
    (net (code "186") (name "TYPEC1_SSTX1P") (class "Default")
      (node (ref "BTB_4") (pin "16") (pinfunction "16_16") (pintype "passive"))
    )
    (net (code "187") (name "TYPEC1_SSTX2N") (class "Default")
      (node (ref "BTB_4") (pin "10") (pinfunction "10_10") (pintype "passive"))
    )
    (net (code "188") (name "TYPEC1_SSTX2P") (class "Default")
      (node (ref "BTB_4") (pin "11") (pinfunction "11_11") (pintype "passive"))
    )
    (net (code "189") (name "TYPEC1_USB20_OTG_DM") (class "Default")
      (node (ref "BTB_4") (pin "70") (pinfunction "70_70") (pintype "passive"))
    )
    (net (code "190") (name "TYPEC1_USB20_OTG_DP") (class "Default")
      (node (ref "BTB_4") (pin "69") (pinfunction "69_69") (pintype "passive"))
    )
    (net (code "191") (name "TYPEC1_USB20_OTG_ID") (class "Default")
      (node (ref "BTB_4") (pin "74") (pinfunction "74_74") (pintype "passive"))
    )
    (net (code "192") (name "TYPEC1_USB20_VBUSDET") (class "Default")
      (node (ref "BTB_4") (pin "67") (pinfunction "67_67") (pintype "passive"))
    )
    (net (code "193") (name "UART2_RX_M0_DEBUG") (class "Default")
      (node (ref "BTB_1") (pin "48") (pinfunction "48_48") (pintype "passive"))
    )
    (net (code "194") (name "UART2_TX_M0_DEBUG") (class "Default")
      (node (ref "BTB_3") (pin "20") (pinfunction "20_20") (pintype "passive"))
    )
    (net (code "195") (name "UART4_RX_M2") (class "Default")
      (node (ref "BTB_3") (pin "45") (pinfunction "45_45") (pintype "passive"))
    )
    (net (code "196") (name "UART4_TX_M2") (class "Default")
      (node (ref "BTB_3") (pin "43") (pinfunction "43_43") (pintype "passive"))
    )
    (net (code "197") (name "UART7_RX_M2") (class "Default")
      (node (ref "BTB_3") (pin "25") (pinfunction "25_25") (pintype "passive"))
    )
    (net (code "198") (name "UART7_TX_M2") (class "Default")
      (node (ref "BTB_3") (pin "49") (pinfunction "49_49") (pintype "passive"))
    )
    (net (code "199") (name "USB20_HOST0_DM") (class "Default")
      (node (ref "BTB_4") (pin "62") (pinfunction "62_62") (pintype "passive"))
    )
    (net (code "200") (name "USB20_HOST0_DP") (class "Default")
      (node (ref "BTB_4") (pin "61") (pinfunction "61_61") (pintype "passive"))
    )
    (net (code "201") (name "USB20_HOST1_DM") (class "Default")
      (node (ref "BTB_4") (pin "65") (pinfunction "65_65") (pintype "passive"))
    )
    (net (code "202") (name "USB20_HOST1_DP") (class "Default")
      (node (ref "BTB_4") (pin "64") (pinfunction "64_64") (pintype "passive"))
    )
    (net (code "203") (name "VCC4V0_SYS") (class "Default")
      (node (ref "BTB_1") (pin "1") (pinfunction "1_1") (pintype "passive"))
      (node (ref "BTB_1") (pin "100") (pinfunction "100_100") (pintype "passive"))
      (node (ref "BTB_1") (pin "2") (pinfunction "2_2") (pintype "passive"))
      (node (ref "BTB_1") (pin "3") (pinfunction "3_3") (pintype "passive"))
      (node (ref "BTB_1") (pin "4") (pinfunction "4_4") (pintype "passive"))
      (node (ref "BTB_1") (pin "5") (pinfunction "5_5") (pintype "passive"))
      (node (ref "BTB_1") (pin "96") (pinfunction "96_96") (pintype "passive"))
      (node (ref "BTB_1") (pin "97") (pinfunction "97_97") (pintype "passive"))
      (node (ref "BTB_1") (pin "98") (pinfunction "98_98") (pintype "passive"))
      (node (ref "BTB_1") (pin "99") (pinfunction "99_99") (pintype "passive"))
      (node (ref "U23") (pin "2") (pinfunction "2_2") (pintype "passive"))
    )
    (net (code "204") (name "VCCA_1V8_S0") (class "Default")
      (node (ref "BTB_1") (pin "10") (pinfunction "10_10") (pintype "passive"))
      (node (ref "BTB_1") (pin "91") (pinfunction "91_91") (pintype "passive"))
    )
    (net (code "205") (name "VCC_1V8_S0") (class "Default")
      (node (ref "BTB_1") (pin "12") (pinfunction "12_12") (pintype "passive"))
      (node (ref "BTB_1") (pin "89") (pinfunction "89_89") (pintype "passive"))
    )
    (net (code "206") (name "VCC_1V8_S3") (class "Default")
      (node (ref "BTB_1") (pin "11") (pinfunction "11_11") (pintype "passive"))
      (node (ref "BTB_1") (pin "90") (pinfunction "90_90") (pintype "passive"))
    )
    (net (code "207") (name "VCC_3V3_S0") (class "Default")
      (node (ref "BTB_1") (pin "9") (pinfunction "9_9") (pintype "passive"))
      (node (ref "BTB_1") (pin "92") (pinfunction "92_92") (pintype "passive"))
    )
    (net (code "208") (name "VCC_3V3_S3") (class "Default")
      (node (ref "BTB_1") (pin "8") (pinfunction "8_8") (pintype "passive"))
      (node (ref "BTB_1") (pin "93") (pinfunction "93_93") (pintype "passive"))
    )
    (net (code "209") (name "unconnected-(BTB_1-Pad21)") (class "Default")
      (node (ref "BTB_1") (pin "21") (pinfunction "21_21") (pintype "passive+no_connect"))
    )
    (net (code "210") (name "unconnected-(BTB_1-Pad22)") (class "Default")
      (node (ref "BTB_1") (pin "22") (pinfunction "22_22") (pintype "passive+no_connect"))
    )
    (net (code "211") (name "unconnected-(BTB_1-Pad24)") (class "Default")
      (node (ref "BTB_1") (pin "24") (pinfunction "24_24") (pintype "passive+no_connect"))
    )
    (net (code "212") (name "unconnected-(BTB_1-Pad25)") (class "Default")
      (node (ref "BTB_1") (pin "25") (pinfunction "25_25") (pintype "passive+no_connect"))
    )
    (net (code "213") (name "unconnected-(BTB_1-Pad26)") (class "Default")
      (node (ref "BTB_1") (pin "26") (pinfunction "26_26") (pintype "passive+no_connect"))
    )
    (net (code "214") (name "unconnected-(BTB_1-Pad27)") (class "Default")
      (node (ref "BTB_1") (pin "27") (pinfunction "27_27") (pintype "passive+no_connect"))
    )
    (net (code "215") (name "unconnected-(BTB_1-Pad29)") (class "Default")
      (node (ref "BTB_1") (pin "29") (pinfunction "29_29") (pintype "passive+no_connect"))
    )
    (net (code "216") (name "unconnected-(BTB_1-Pad30)") (class "Default")
      (node (ref "BTB_1") (pin "30") (pinfunction "30_30") (pintype "passive+no_connect"))
    )
    (net (code "217") (name "unconnected-(BTB_1-Pad32)") (class "Default")
      (node (ref "BTB_1") (pin "32") (pinfunction "32_32") (pintype "passive+no_connect"))
    )
    (net (code "218") (name "unconnected-(BTB_1-Pad33)") (class "Default")
      (node (ref "BTB_1") (pin "33") (pinfunction "33_33") (pintype "passive+no_connect"))
    )
    (net (code "219") (name "unconnected-(BTB_1-Pad34)") (class "Default")
      (node (ref "BTB_1") (pin "34") (pinfunction "34_34") (pintype "passive+no_connect"))
    )
    (net (code "220") (name "unconnected-(BTB_1-Pad35)") (class "Default")
      (node (ref "BTB_1") (pin "35") (pinfunction "35_35") (pintype "passive+no_connect"))
    )
    (net (code "221") (name "unconnected-(BTB_1-Pad67)") (class "Default")
      (node (ref "BTB_1") (pin "67") (pinfunction "67_67") (pintype "passive+no_connect"))
    )
    (net (code "222") (name "unconnected-(BTB_1-Pad68)") (class "Default")
      (node (ref "BTB_1") (pin "68") (pinfunction "68_68") (pintype "passive+no_connect"))
    )
    (net (code "223") (name "unconnected-(BTB_1-Pad69)") (class "Default")
      (node (ref "BTB_1") (pin "69") (pinfunction "69_69") (pintype "passive+no_connect"))
    )
    (net (code "224") (name "unconnected-(BTB_1-Pad70)") (class "Default")
      (node (ref "BTB_1") (pin "70") (pinfunction "70_70") (pintype "passive+no_connect"))
    )
    (net (code "225") (name "unconnected-(BTB_1-Pad72)") (class "Default")
      (node (ref "BTB_1") (pin "72") (pinfunction "72_72") (pintype "passive+no_connect"))
    )
    (net (code "226") (name "unconnected-(BTB_1-Pad73)") (class "Default")
      (node (ref "BTB_1") (pin "73") (pinfunction "73_73") (pintype "passive+no_connect"))
    )
    (net (code "227") (name "unconnected-(BTB_1-Pad75)") (class "Default")
      (node (ref "BTB_1") (pin "75") (pinfunction "75_75") (pintype "passive+no_connect"))
    )
    (net (code "228") (name "unconnected-(BTB_1-Pad76)") (class "Default")
      (node (ref "BTB_1") (pin "76") (pinfunction "76_76") (pintype "passive+no_connect"))
    )
    (net (code "229") (name "unconnected-(BTB_1-Pad77)") (class "Default")
      (node (ref "BTB_1") (pin "77") (pinfunction "77_77") (pintype "passive+no_connect"))
    )
    (net (code "230") (name "unconnected-(BTB_1-Pad78)") (class "Default")
      (node (ref "BTB_1") (pin "78") (pinfunction "78_78") (pintype "passive+no_connect"))
    )
    (net (code "231") (name "unconnected-(BTB_1-Pad80)") (class "Default")
      (node (ref "BTB_1") (pin "80") (pinfunction "80_80") (pintype "passive+no_connect"))
    )
    (net (code "232") (name "unconnected-(BTB_1-Pad81)") (class "Default")
      (node (ref "BTB_1") (pin "81") (pinfunction "81_81") (pintype "passive+no_connect"))
    )
    (net (code "233") (name "unconnected-(BTB_2-Pad33)") (class "Default")
      (node (ref "BTB_2") (pin "33") (pinfunction "33_33") (pintype "passive+no_connect"))
    )
    (net (code "234") (name "unconnected-(BTB_2-Pad34)") (class "Default")
      (node (ref "BTB_2") (pin "34") (pinfunction "34_34") (pintype "passive+no_connect"))
    )
    (net (code "235") (name "unconnected-(BTB_2-Pad35)") (class "Default")
      (node (ref "BTB_2") (pin "35") (pinfunction "35_35") (pintype "passive+no_connect"))
    )
    (net (code "236") (name "unconnected-(BTB_2-Pad36)") (class "Default")
      (node (ref "BTB_2") (pin "36") (pinfunction "36_36") (pintype "passive+no_connect"))
    )
    (net (code "237") (name "unconnected-(BTB_2-Pad38)") (class "Default")
      (node (ref "BTB_2") (pin "38") (pinfunction "38_38") (pintype "passive+no_connect"))
    )
    (net (code "238") (name "unconnected-(BTB_2-Pad39)") (class "Default")
      (node (ref "BTB_2") (pin "39") (pinfunction "39_39") (pintype "passive+no_connect"))
    )
    (net (code "239") (name "unconnected-(BTB_2-Pad41)") (class "Default")
      (node (ref "BTB_2") (pin "41") (pinfunction "41_41") (pintype "passive+no_connect"))
    )
    (net (code "240") (name "unconnected-(BTB_2-Pad42)") (class "Default")
      (node (ref "BTB_2") (pin "42") (pinfunction "42_42") (pintype "passive+no_connect"))
    )
    (net (code "241") (name "unconnected-(BTB_2-Pad43)") (class "Default")
      (node (ref "BTB_2") (pin "43") (pinfunction "43_43") (pintype "passive+no_connect"))
    )
    (net (code "242") (name "unconnected-(BTB_2-Pad44)") (class "Default")
      (node (ref "BTB_2") (pin "44") (pinfunction "44_44") (pintype "passive+no_connect"))
    )
    (net (code "243") (name "unconnected-(BTB_2-Pad52)") (class "Default")
      (node (ref "BTB_2") (pin "52") (pinfunction "52_52") (pintype "passive+no_connect"))
    )
    (net (code "244") (name "unconnected-(BTB_2-Pad53)") (class "Default")
      (node (ref "BTB_2") (pin "53") (pinfunction "53_53") (pintype "passive+no_connect"))
    )
    (net (code "245") (name "unconnected-(BTB_2-Pad54)") (class "Default")
      (node (ref "BTB_2") (pin "54") (pinfunction "54_54") (pintype "passive+no_connect"))
    )
    (net (code "246") (name "unconnected-(BTB_2-Pad55)") (class "Default")
      (node (ref "BTB_2") (pin "55") (pinfunction "55_55") (pintype "passive+no_connect"))
    )
    (net (code "247") (name "unconnected-(BTB_2-Pad56)") (class "Default")
      (node (ref "BTB_2") (pin "56") (pinfunction "56_56") (pintype "passive+no_connect"))
    )
    (net (code "248") (name "unconnected-(BTB_2-Pad57)") (class "Default")
      (node (ref "BTB_2") (pin "57") (pinfunction "57_57") (pintype "passive+no_connect"))
    )
    (net (code "249") (name "unconnected-(BTB_2-Pad58)") (class "Default")
      (node (ref "BTB_2") (pin "58") (pinfunction "58_58") (pintype "passive+no_connect"))
    )
    (net (code "250") (name "unconnected-(BTB_2-Pad59)") (class "Default")
      (node (ref "BTB_2") (pin "59") (pinfunction "59_59") (pintype "passive+no_connect"))
    )
    (net (code "251") (name "unconnected-(BTB_2-Pad60)") (class "Default")
      (node (ref "BTB_2") (pin "60") (pinfunction "60_60") (pintype "passive+no_connect"))
    )
    (net (code "252") (name "unconnected-(BTB_2-Pad61)") (class "Default")
      (node (ref "BTB_2") (pin "61") (pinfunction "61_61") (pintype "passive+no_connect"))
    )
    (net (code "253") (name "unconnected-(BTB_2-Pad62)") (class "Default")
      (node (ref "BTB_2") (pin "62") (pinfunction "62_62") (pintype "passive+no_connect"))
    )
    (net (code "254") (name "unconnected-(BTB_2-Pad63)") (class "Default")
      (node (ref "BTB_2") (pin "63") (pinfunction "63_63") (pintype "passive+no_connect"))
    )
    (net (code "255") (name "unconnected-(BTB_2-Pad64)") (class "Default")
      (node (ref "BTB_2") (pin "64") (pinfunction "64_64") (pintype "passive+no_connect"))
    )
    (net (code "256") (name "unconnected-(BTB_2-Pad67)") (class "Default")
      (node (ref "BTB_2") (pin "67") (pinfunction "67_67") (pintype "passive+no_connect"))
    )
    (net (code "257") (name "unconnected-(BTB_2-Pad69)") (class "Default")
      (node (ref "BTB_2") (pin "69") (pinfunction "69_69") (pintype "passive+no_connect"))
    )
    (net (code "258") (name "unconnected-(BTB_2-Pad70)") (class "Default")
      (node (ref "BTB_2") (pin "70") (pinfunction "70_70") (pintype "passive+no_connect"))
    )
    (net (code "259") (name "unconnected-(BTB_2-Pad76)") (class "Default")
      (node (ref "BTB_2") (pin "76") (pinfunction "76_76") (pintype "passive+no_connect"))
    )
    (net (code "260") (name "unconnected-(BTB_2-Pad78)") (class "Default")
      (node (ref "BTB_2") (pin "78") (pinfunction "78_78") (pintype "passive+no_connect"))
    )
    (net (code "261") (name "unconnected-(BTB_2-Pad80)") (class "Default")
      (node (ref "BTB_2") (pin "80") (pinfunction "80_80") (pintype "passive+no_connect"))
    )
    (net (code "262") (name "unconnected-(BTB_2-Pad82)") (class "Default")
      (node (ref "BTB_2") (pin "82") (pinfunction "82_82") (pintype "passive+no_connect"))
    )
    (net (code "263") (name "unconnected-(BTB_2-Pad83)") (class "Default")
      (node (ref "BTB_2") (pin "83") (pinfunction "83_83") (pintype "passive+no_connect"))
    )
    (net (code "264") (name "unconnected-(BTB_2-Pad85)") (class "Default")
      (node (ref "BTB_2") (pin "85") (pinfunction "85_85") (pintype "passive+no_connect"))
    )
    (net (code "265") (name "unconnected-(BTB_2-Pad86)") (class "Default")
      (node (ref "BTB_2") (pin "86") (pinfunction "86_86") (pintype "passive+no_connect"))
    )
    (net (code "266") (name "unconnected-(BTB_2-Pad87)") (class "Default")
      (node (ref "BTB_2") (pin "87") (pinfunction "87_87") (pintype "passive+no_connect"))
    )
    (net (code "267") (name "unconnected-(BTB_2-Pad90)") (class "Default")
      (node (ref "BTB_2") (pin "90") (pinfunction "90_90") (pintype "passive+no_connect"))
    )
    (net (code "268") (name "unconnected-(BTB_2-Pad91)") (class "Default")
      (node (ref "BTB_2") (pin "91") (pinfunction "91_91") (pintype "passive+no_connect"))
    )
    (net (code "269") (name "unconnected-(BTB_3-Pad6)") (class "Default")
      (node (ref "BTB_3") (pin "6") (pinfunction "6_6") (pintype "passive+no_connect"))
    )
    (net (code "270") (name "unconnected-(BTB_3-Pad14)") (class "Default")
      (node (ref "BTB_3") (pin "14") (pinfunction "14_14") (pintype "passive+no_connect"))
    )
    (net (code "271") (name "unconnected-(BTB_3-Pad57)") (class "Default")
      (node (ref "BTB_3") (pin "57") (pinfunction "57_57") (pintype "passive+no_connect"))
    )
    (net (code "272") (name "unconnected-(BTB_4-Pad52)") (class "Default")
      (node (ref "BTB_4") (pin "52") (pinfunction "52_52") (pintype "passive+no_connect"))
    )
    (net (code "273") (name "unconnected-(BTB_4-Pad53)") (class "Default")
      (node (ref "BTB_4") (pin "53") (pinfunction "53_53") (pintype "passive+no_connect"))
    )
    (net (code "274") (name "unconnected-(BTB_4-Pad54)") (class "Default")
      (node (ref "BTB_4") (pin "54") (pinfunction "54_54") (pintype "passive+no_connect"))
    )
    (net (code "275") (name "unconnected-(BTB_4-Pad55)") (class "Default")
      (node (ref "BTB_4") (pin "55") (pinfunction "55_55") (pintype "passive+no_connect"))
    )
    (net (code "276") (name "unconnected-(BTB_4-Pad56)") (class "Default")
      (node (ref "BTB_4") (pin "56") (pinfunction "56_56") (pintype "passive+no_connect"))
    )
    (net (code "277") (name "unconnected-(BTB_4-Pad57)") (class "Default")
      (node (ref "BTB_4") (pin "57") (pinfunction "57_57") (pintype "passive+no_connect"))
    )
    (net (code "278") (name "unconnected-(BTB_4-Pad58)") (class "Default")
      (node (ref "BTB_4") (pin "58") (pinfunction "58_58") (pintype "passive+no_connect"))
    )
    (net (code "279") (name "unconnected-(BTB_4-Pad59)") (class "Default")
      (node (ref "BTB_4") (pin "59") (pinfunction "59_59") (pintype "passive+no_connect"))
    )
  )
)
